# HDMI.net
KiCad netlist of a schematic drawn in Altium Designer
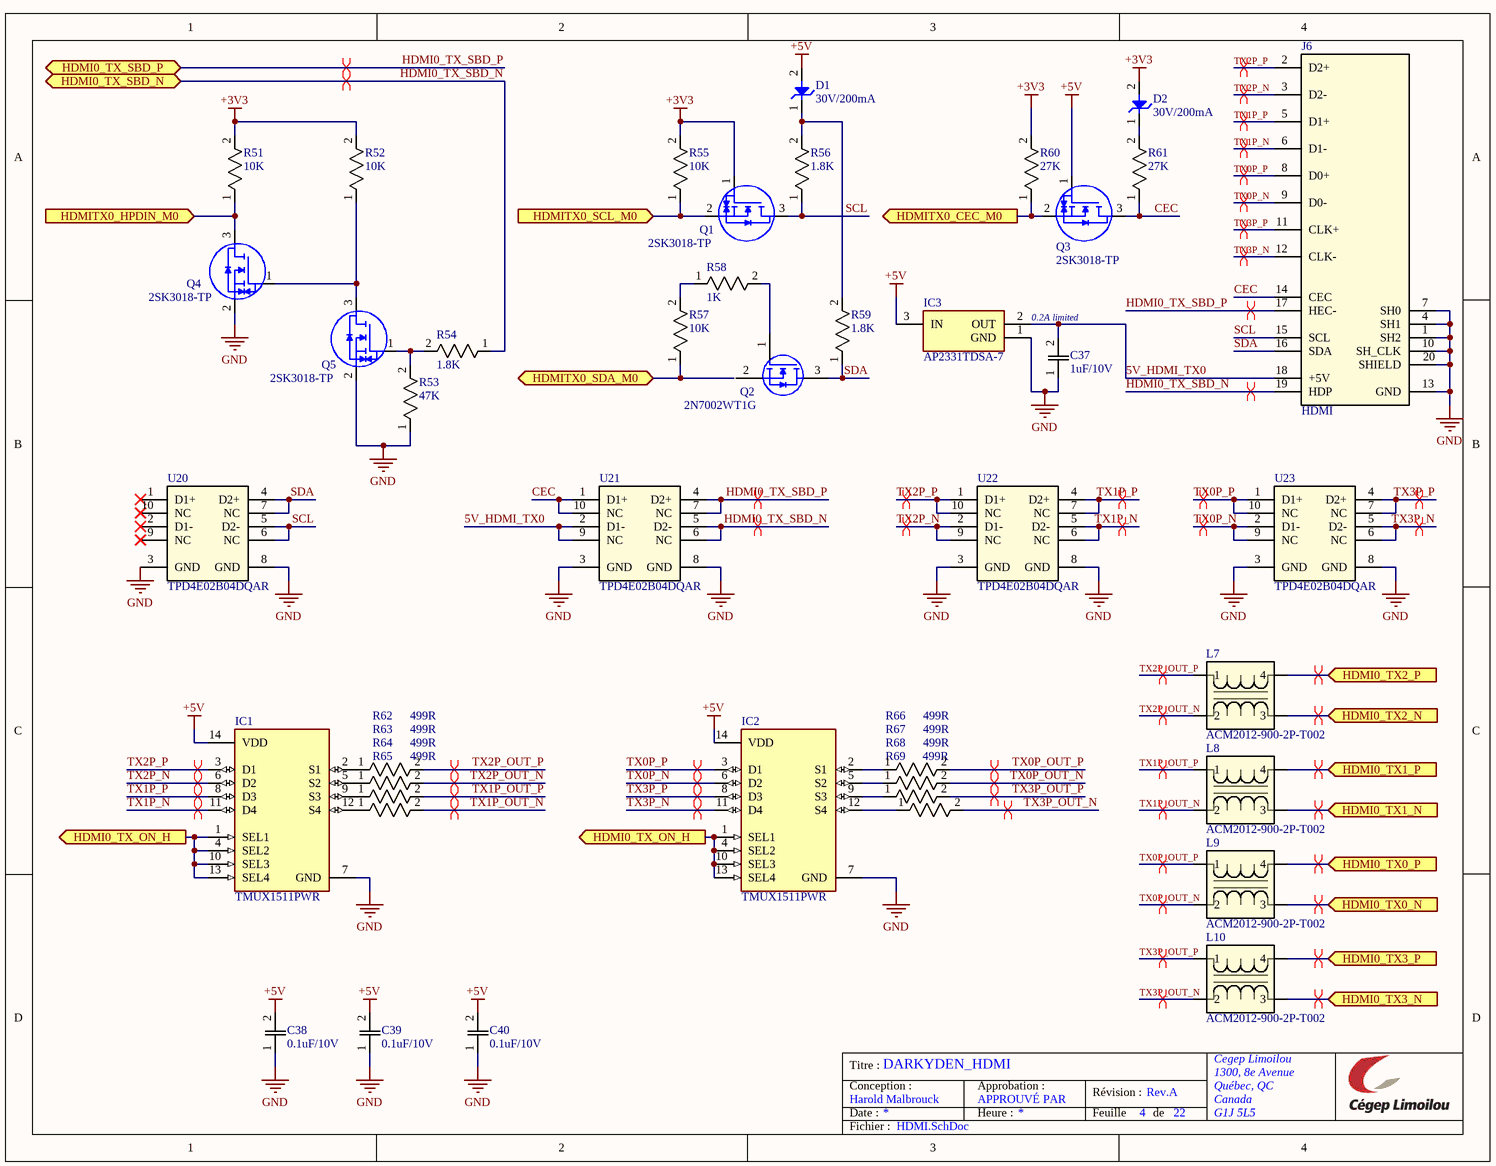
[diagram p0: HDMI.SchDoc]

(export (version "E")
  (design (tool "Eeschema 10.0.6"))
  (components
    (comp (ref "C37")
      (value "1uF/10V")
      (footprint "C0805")
      (description "Multilayer Ceramic Capacitors MLCC - SMD/SMT 10V 1uF X7R 0805 10%")
      (fields
        (field (name "MANUFACTURER") "KEMET")
        (field (name "MANUFACTURER PART NUMBER") "C0805C105K8RACTU")
      )
      (libsource (lib "DARKYDEN") (part "C0805C105K8RACTU"))
    )
    (comp (ref "C38")
      (value "0.1uF/10V")
      (footprint "c0805")
      (description "Cap Ceramic 0.1uF 10V X7R 5% Pad SMD 0805 125C T/R")
      (fields
        (field (name "MANUFACTURER") "KEMET")
        (field (name "MANUFACTURER PART NUMBER") "C0805C104J8RACTU")
      )
      (libsource (lib "DARKYDEN") (part "C0805C104J8RACTU"))
    )
    (comp (ref "C39")
      (value "0.1uF/10V")
      (footprint "c0805")
      (description "Cap Ceramic 0.1uF 10V X7R 5% Pad SMD 0805 125C T/R")
      (fields
        (field (name "MANUFACTURER") "KEMET")
        (field (name "MANUFACTURER PART NUMBER") "C0805C104J8RACTU")
      )
      (libsource (lib "DARKYDEN") (part "C0805C104J8RACTU"))
    )
    (comp (ref "C40")
      (value "0.1uF/10V")
      (footprint "c0805")
      (description "Cap Ceramic 0.1uF 10V X7R 5% Pad SMD 0805 125C T/R")
      (fields
        (field (name "MANUFACTURER") "KEMET")
        (field (name "MANUFACTURER PART NUMBER") "C0805C104J8RACTU")
      )
      (libsource (lib "DARKYDEN") (part "C0805C104J8RACTU"))
    )
    (comp (ref "D1")
      (value "30V/200mA")
      (footprint "SamacSys:SODFL1608X70N")
      (description "SCHOTTKY BARRIER DIODE Rectifier Diode, Schottky, 1 Phase, 1 Element, 0.2A, 30V V(RRM), Silicon")
      (fields
        (field (name "MANUFACTURER_PART_NUMBER") "RB521S30T1G")
        (field (name "MOUSER PART NUMBER") "863-RB521S30T1G")
      )
      (libsource (lib "SamacSys") (part "RB521S30T1G"))
    )
    (comp (ref "D2")
      (value "30V/200mA")
      (footprint "SamacSys:SODFL1608X70N")
      (description "SCHOTTKY BARRIER DIODE Rectifier Diode, Schottky, 1 Phase, 1 Element, 0.2A, 30V V(RRM), Silicon")
      (fields
        (field (name "MANUFACTURER_PART_NUMBER") "RB521S30T1G")
        (field (name "MOUSER PART NUMBER") "863-RB521S30T1G")
      )
      (libsource (lib "SamacSys") (part "RB521S30T1G"))
    )
    (comp (ref "IC1")
      (value "TMUX1511PWR")
      (footprint "SamacSys:SOP65P640X120-14N")
      (fields
        (field (name "MOUSER PART NUMBER") "595-TMUX1511PWR")
        (field (name "MANUFACTURER") "Texas Instruments")
      )
      (libsource (lib "SamacSys") (part "TMUX1511PWR"))
    )
    (comp (ref "IC2")
      (value "TMUX1511PWR")
      (footprint "SamacSys:SOP65P640X120-14N")
      (fields
        (field (name "MOUSER PART NUMBER") "595-TMUX1511PWR")
        (field (name "MANUFACTURER") "Texas Instruments")
      )
      (libsource (lib "SamacSys") (part "TMUX1511PWR"))
    )
    (comp (ref "IC3")
      (value "AP2331TDSA-7")
      (footprint "SamacSys:SOT96P240X110-3N")
      (description "USB Power Switch Single 5.2V 0.4A 3-Pin SOT-23 T/R")
      (fields (field (name "MOUSER PART NUMBER") "621-AP2331TDSA-7") (field (name "MANUFACTURER") "Diodes"))
      (libsource (lib "SamacSys") (part "AP2331TDSA-7"))
    )
    (comp (ref "J6")
      (value "HDMI")
      (footprint "HDMI_MINI")
      (description "Conn Mini HDMI PL 19 POS 0.4mm Solder RA SMD 19 Terminal 1 Port T/R")
      (fields
        (field (name "MANUFACTURER") "Wurth Electronics")
        (field (name "MANUFACTURER PART NUMBER") "685119136923")
      )
      (libsource (lib "DARKYDEN") (part "HDMI"))
    )
    (comp (ref "L7")
      (value "ACM2012-900-2P-T002")
      (footprint "SamacSys:ACM20129002PT002")
      (description "Ferrite Beads Wirewound Common Mode Filter 90Ohm 100MHz 400mA 0805 T/R")
      (fields (field (name "MOUSER PART NUMBER") "810-ACM20129002PT002") (field (name "MANUFACTURER") "TDK"))
      (libsource (lib "SamacSys") (part "ACM2012-900-2P-T002"))
    )
    (comp (ref "L8")
      (value "ACM2012-900-2P-T002")
      (footprint "SamacSys:ACM20129002PT002")
      (description "Ferrite Beads Wirewound Common Mode Filter 90Ohm 100MHz 400mA 0805 T/R")
      (fields (field (name "MOUSER PART NUMBER") "810-ACM20129002PT002") (field (name "MANUFACTURER") "TDK"))
      (libsource (lib "SamacSys") (part "ACM2012-900-2P-T002"))
    )
    (comp (ref "L9")
      (value "ACM2012-900-2P-T002")
      (footprint "SamacSys:ACM20129002PT002")
      (description "Ferrite Beads Wirewound Common Mode Filter 90Ohm 100MHz 400mA 0805 T/R")
      (fields (field (name "MOUSER PART NUMBER") "810-ACM20129002PT002") (field (name "MANUFACTURER") "TDK"))
      (libsource (lib "SamacSys") (part "ACM2012-900-2P-T002"))
    )
    (comp (ref "L10")
      (value "ACM2012-900-2P-T002")
      (footprint "SamacSys:ACM20129002PT002")
      (description "Ferrite Beads Wirewound Common Mode Filter 90Ohm 100MHz 400mA 0805 T/R")
      (fields (field (name "MOUSER PART NUMBER") "810-ACM20129002PT002") (field (name "MANUFACTURER") "TDK"))
      (libsource (lib "SamacSys") (part "ACM2012-900-2P-T002"))
    )
    (comp (ref "Q1")
      (value "2SK3018-TP")
      (footprint "SamacSys:SOT65P228X120-3N")
      (description "N-Channel 30 V 100mA (Ta) 200mW (Ta) Surface Mount SOT-323")
      (fields (field (name "MOUSER PART NUMBER") "833-2SK3018-TP"))
      (libsource (lib "SamacSys") (part "2SK3018-TP"))
    )
    (comp (ref "Q2")
      (value "2N7002WT1G")
      (footprint "SOT-323-3_2P2X1P35_ONS")
      (description "No Description Available")
      (libsource (lib "2N7002WT1G") (part "2N7002WT1G"))
    )
    (comp (ref "Q3")
      (value "2SK3018-TP")
      (footprint "SamacSys:SOT65P228X120-3N")
      (description "N-Channel 30 V 100mA (Ta) 200mW (Ta) Surface Mount SOT-323")
      (fields (field (name "MOUSER PART NUMBER") "833-2SK3018-TP"))
      (libsource (lib "SamacSys") (part "2SK3018-TP"))
    )
    (comp (ref "Q4")
      (value "2SK3018-TP")
      (footprint "SamacSys:SOT65P228X120-3N")
      (description "N-Channel 30 V 100mA (Ta) 200mW (Ta) Surface Mount SOT-323")
      (fields (field (name "MOUSER PART NUMBER") "833-2SK3018-TP"))
      (libsource (lib "SamacSys") (part "2SK3018-TP"))
    )
    (comp (ref "Q5")
      (value "2SK3018-TP")
      (footprint "SamacSys:SOT65P228X120-3N")
      (description "N-Channel 30 V 100mA (Ta) 200mW (Ta) Surface Mount SOT-323")
      (fields (field (name "MOUSER PART NUMBER") "833-2SK3018-TP"))
      (libsource (lib "SamacSys") (part "2SK3018-TP"))
    )
    (comp (ref "R51")
      (value "10K")
      (footprint "SamacSys:RESC1608X55N")
      (description "10K Ohm 5% Res Thick Film 0603  0.1W(1/10W) ±200ppm/C Pad SMD Automotive T/R")
      (fields
        (field (name "MANUFACTURER_PART_NUMBER") "ERJ-3GEYJ103V")
        (field (name "MOUSER PART NUMBER") "667-ERJ-3GEYJ103V")
      )
      (libsource (lib "DARKYDEN") (part "ERJ-3GEYJ103V"))
    )
    (comp (ref "R52")
      (value "10K")
      (footprint "SamacSys:RESC1608X55N")
      (description "10K Ohm 5% Res Thick Film 0603  0.1W(1/10W) ±200ppm/C Pad SMD Automotive T/R")
      (fields
        (field (name "MANUFACTURER_PART_NUMBER") "ERJ-3GEYJ103V")
        (field (name "MOUSER PART NUMBER") "667-ERJ-3GEYJ103V")
      )
      (libsource (lib "DARKYDEN") (part "ERJ-3GEYJ103V"))
    )
    (comp (ref "R53")
      (value "47K")
      (footprint "RESC1608X55N")
      (description "47K Ohm 5% 1/10W 0603 200ppm/C Molded SMD Punched Carrier T/R")
      (fields
        (field (name "MANUFACTURER") "Panasonic")
        (field (name "MANUFACTURER PART NUMBER") "ERJ-3GEYJ473V")
      )
      (libsource (lib "DARKYDEN") (part "ERJ-3GEYJ473V"))
    )
    (comp (ref "R54")
      (value "1.8K")
      (footprint "RESC1608X55N")
      (description "1.8 kOhm, ± 5%, 100 mW, 0603 [1608 Metric], Thick Film, General Purpose")
      (fields
        (field (name "MANUFACTURER") "Panasonic")
        (field (name "MANUFACTURER PART NUMBER") "ERJ-3GEYJ182V")
      )
      (libsource (lib "DARKYDEN") (part "ERJ-3GEYJ182V"))
    )
    (comp (ref "R55")
      (value "10K")
      (footprint "SamacSys:RESC1608X55N")
      (description "10K Ohm 5% Res Thick Film 0603  0.1W(1/10W) ±200ppm/C Pad SMD Automotive T/R")
      (fields
        (field (name "MANUFACTURER_PART_NUMBER") "ERJ-3GEYJ103V")
        (field (name "MOUSER PART NUMBER") "667-ERJ-3GEYJ103V")
      )
      (libsource (lib "DARKYDEN") (part "ERJ-3GEYJ103V"))
    )
    (comp (ref "R56")
      (value "1.8K")
      (footprint "RESC1608X55N")
      (description "1.8 kOhm, ± 5%, 100 mW, 0603 [1608 Metric], Thick Film, General Purpose")
      (fields
        (field (name "MANUFACTURER") "Panasonic")
        (field (name "MANUFACTURER PART NUMBER") "ERJ-3GEYJ182V")
      )
      (libsource (lib "DARKYDEN") (part "ERJ-3GEYJ182V"))
    )
    (comp (ref "R57")
      (value "10K")
      (footprint "SamacSys:RESC1608X55N")
      (description "10K Ohm 5% Res Thick Film 0603  0.1W(1/10W) ±200ppm/C Pad SMD Automotive T/R")
      (fields
        (field (name "MANUFACTURER_PART_NUMBER") "ERJ-3GEYJ103V")
        (field (name "MOUSER PART NUMBER") "667-ERJ-3GEYJ103V")
      )
      (libsource (lib "DARKYDEN") (part "ERJ-3GEYJ103V"))
    )
    (comp (ref "R58")
      (value "1K")
      (footprint "SamacSys:RESC1608X55N")
      (description "1K Ohm 1% 1/10W Res Thick Film 0603 ±100ppm/°C Molded SMD Punched Carrier T/R")
      (fields
        (field (name "MANUFACTURER_PART_NUMBER") "ERJ-3EKF1001V")
        (field (name "MOUSER PART NUMBER") "667-ERJ-3EKF1001V")
      )
      (libsource (lib "DARKYDEN") (part "ERJ-3EKF1001V"))
    )
    (comp (ref "R59")
      (value "1.8K")
      (footprint "RESC1608X55N")
      (description "1.8 kOhm, ± 5%, 100 mW, 0603 [1608 Metric], Thick Film, General Purpose")
      (fields
        (field (name "MANUFACTURER") "Panasonic")
        (field (name "MANUFACTURER PART NUMBER") "ERJ-3GEYJ182V")
      )
      (libsource (lib "DARKYDEN") (part "ERJ-3GEYJ182V"))
    )
    (comp (ref "R60")
      (value "27K")
      (footprint "RESC1608X55N")
      (description "27K Ohm 1% 1/10W 0603 ±100ppm/°C Molded SMD Punched Carrier T/R")
      (fields
        (field (name "MANUFACTURER") "Panasonic")
        (field (name "MANUFACTURER PART NUMBER") "ERJ-3EKF2702V")
      )
      (libsource (lib "DARKYDEN") (part "ERJ-3EKF2702V"))
    )
    (comp (ref "R61")
      (value "27K")
      (footprint "RESC1608X55N")
      (description "27K Ohm 1% 1/10W 0603 ±100ppm/°C Molded SMD Punched Carrier T/R")
      (fields
        (field (name "MANUFACTURER") "Panasonic")
        (field (name "MANUFACTURER PART NUMBER") "ERJ-3EKF2702V")
      )
      (libsource (lib "DARKYDEN") (part "ERJ-3EKF2702V"))
    )
    (comp (ref "R62")
      (value "499R")
      (footprint "RESC1608X55N")
      (description "499 Ohm, ï¿½ 1%, 100 mW, 0603 [1608 Metric], Thick Film, Precision")
      (fields
        (field (name "MANUFACTURER") "Panasonic")
        (field (name "MANUFACTURER PART NUMBER") "ERJ-3EKF4990V")
      )
      (libsource (lib "DARKYDEN") (part "ERJ-3EKF4990V"))
    )
    (comp (ref "R63")
      (value "499R")
      (footprint "RESC1608X55N")
      (description "499 Ohm, ï¿½ 1%, 100 mW, 0603 [1608 Metric], Thick Film, Precision")
      (fields
        (field (name "MANUFACTURER") "Panasonic")
        (field (name "MANUFACTURER PART NUMBER") "ERJ-3EKF4990V")
      )
      (libsource (lib "DARKYDEN") (part "ERJ-3EKF4990V"))
    )
    (comp (ref "R64")
      (value "499R")
      (footprint "RESC1608X55N")
      (description "499 Ohm, ï¿½ 1%, 100 mW, 0603 [1608 Metric], Thick Film, Precision")
      (fields
        (field (name "MANUFACTURER") "Panasonic")
        (field (name "MANUFACTURER PART NUMBER") "ERJ-3EKF4990V")
      )
      (libsource (lib "DARKYDEN") (part "ERJ-3EKF4990V"))
    )
    (comp (ref "R65")
      (value "499R")
      (footprint "RESC1608X55N")
      (description "499 Ohm, ï¿½ 1%, 100 mW, 0603 [1608 Metric], Thick Film, Precision")
      (fields
        (field (name "MANUFACTURER") "Panasonic")
        (field (name "MANUFACTURER PART NUMBER") "ERJ-3EKF4990V")
      )
      (libsource (lib "DARKYDEN") (part "ERJ-3EKF4990V"))
    )
    (comp (ref "R66")
      (value "499R")
      (footprint "RESC1608X55N")
      (description "499 Ohm, ï¿½ 1%, 100 mW, 0603 [1608 Metric], Thick Film, Precision")
      (fields
        (field (name "MANUFACTURER") "Panasonic")
        (field (name "MANUFACTURER PART NUMBER") "ERJ-3EKF4990V")
      )
      (libsource (lib "DARKYDEN") (part "ERJ-3EKF4990V"))
    )
    (comp (ref "R67")
      (value "499R")
      (footprint "RESC1608X55N")
      (description "499 Ohm, ï¿½ 1%, 100 mW, 0603 [1608 Metric], Thick Film, Precision")
      (fields
        (field (name "MANUFACTURER") "Panasonic")
        (field (name "MANUFACTURER PART NUMBER") "ERJ-3EKF4990V")
      )
      (libsource (lib "DARKYDEN") (part "ERJ-3EKF4990V"))
    )
    (comp (ref "R68")
      (value "499R")
      (footprint "RESC1608X55N")
      (description "499 Ohm, ï¿½ 1%, 100 mW, 0603 [1608 Metric], Thick Film, Precision")
      (fields
        (field (name "MANUFACTURER") "Panasonic")
        (field (name "MANUFACTURER PART NUMBER") "ERJ-3EKF4990V")
      )
      (libsource (lib "DARKYDEN") (part "ERJ-3EKF4990V"))
    )
    (comp (ref "R69")
      (value "499R")
      (footprint "RESC1608X55N")
      (description "499 Ohm, ï¿½ 1%, 100 mW, 0603 [1608 Metric], Thick Film, Precision")
      (fields
        (field (name "MANUFACTURER") "Panasonic")
        (field (name "MANUFACTURER PART NUMBER") "ERJ-3EKF4990V")
      )
      (libsource (lib "DARKYDEN") (part "ERJ-3EKF4990V"))
    )
    (comp (ref "U20")
      (value "TPD4E02B04DQAR")
      (footprint "DQA0010A")
      (description "TVS DIODE 3.6V 8.8V 10USON / 4-Channel ESD Protection Diode for USB Type-C and HDMI 2.0")
      (fields (field (name "MANUFACTURER") "Texas Instruments"))
      (libsource (lib "TPD4E02B04DQAR") (part "TPD4E02B04DQAR"))
    )
    (comp (ref "U21")
      (value "TPD4E02B04DQAR")
      (footprint "DQA0010A")
      (description "TVS DIODE 3.6V 8.8V 10USON / 4-Channel ESD Protection Diode for USB Type-C and HDMI 2.0")
      (fields (field (name "MANUFACTURER") "Texas Instruments"))
      (libsource (lib "TPD4E02B04DQAR") (part "TPD4E02B04DQAR"))
    )
    (comp (ref "U22")
      (value "TPD4E02B04DQAR")
      (footprint "DQA0010A")
      (description "TVS DIODE 3.6V 8.8V 10USON / 4-Channel ESD Protection Diode for USB Type-C and HDMI 2.0")
      (fields (field (name "MANUFACTURER") "Texas Instruments"))
      (libsource (lib "TPD4E02B04DQAR") (part "TPD4E02B04DQAR"))
    )
    (comp (ref "U23")
      (value "TPD4E02B04DQAR")
      (footprint "DQA0010A")
      (description "TVS DIODE 3.6V 8.8V 10USON / 4-Channel ESD Protection Diode for USB Type-C and HDMI 2.0")
      (fields (field (name "MANUFACTURER") "Texas Instruments"))
      (libsource (lib "TPD4E02B04DQAR") (part "TPD4E02B04DQAR"))
    )
  )
  (nets
    (net (code "1") (name "+3V3") (class "Default")
      (node (ref "D2") (pin "2") (pinfunction "A_2") (pintype "passive"))
      (node (ref "Q1") (pin "1") (pinfunction "G_1") (pintype "passive"))
      (node (ref "R51") (pin "2") (pinfunction "2_2") (pintype "passive"))
      (node (ref "R52") (pin "2") (pinfunction "2_2") (pintype "passive"))
      (node (ref "R55") (pin "2") (pinfunction "2_2") (pintype "passive"))
      (node (ref "R60") (pin "2") (pinfunction "2_2") (pintype "passive"))
    )
    (net (code "2") (name "+5V") (class "Default")
      (node (ref "C38") (pin "2") (pinfunction "2_2") (pintype "passive"))
      (node (ref "C39") (pin "2") (pinfunction "2_2") (pintype "passive"))
      (node (ref "C40") (pin "2") (pinfunction "2_2") (pintype "passive"))
      (node (ref "D1") (pin "2") (pinfunction "A_2") (pintype "passive"))
      (node (ref "IC1") (pin "14") (pinfunction "VDD_14") (pintype "power_in"))
      (node (ref "IC2") (pin "14") (pinfunction "VDD_14") (pintype "power_in"))
      (node (ref "IC3") (pin "3") (pinfunction "IN_3") (pintype "passive"))
      (node (ref "Q3") (pin "1") (pinfunction "G_1") (pintype "passive"))
    )
    (net (code "3") (name "/5V_HDMI_TX0") (class "Default")
      (node (ref "C37") (pin "2") (pinfunction "2_2") (pintype "passive"))
      (node (ref "IC3") (pin "2") (pinfunction "OUT_2") (pintype "passive"))
      (node (ref "J6") (pin "18") (pinfunction "+5V_18") (pintype "passive"))
      (node (ref "U21") (pin "2") (pinfunction "D1-_2") (pintype "passive"))
      (node (ref "U21") (pin "9") (pinfunction "NC_9") (pintype "passive"))
    )
    (net (code "4") (name "/CEC") (class "Default")
      (node (ref "J6") (pin "14") (pinfunction "CEC_14") (pintype "passive"))
      (node (ref "Q3") (pin "3") (pinfunction "D_3") (pintype "passive"))
      (node (ref "R61") (pin "1") (pinfunction "1_1") (pintype "passive"))
      (node (ref "U21") (pin "1") (pinfunction "D1+_1") (pintype "passive"))
      (node (ref "U21") (pin "10") (pinfunction "NC_10") (pintype "passive"))
    )
    (net (code "5") (name "/HDMI0_TX0_N") (class "Default")
      (node (ref "L9") (pin "3") (pinfunction "3_3") (pintype "passive"))
    )
    (net (code "6") (name "/HDMI0_TX0_P") (class "Default")
      (node (ref "L9") (pin "4") (pinfunction "4_4") (pintype "passive"))
    )
    (net (code "7") (name "/HDMI0_TX1_N") (class "Default")
      (node (ref "L8") (pin "3") (pinfunction "3_3") (pintype "passive"))
    )
    (net (code "8") (name "/HDMI0_TX1_P") (class "Default")
      (node (ref "L8") (pin "4") (pinfunction "4_4") (pintype "passive"))
    )
    (net (code "9") (name "/HDMI0_TX2_N") (class "Default")
      (node (ref "L7") (pin "3") (pinfunction "3_3") (pintype "passive"))
    )
    (net (code "10") (name "/HDMI0_TX2_P") (class "Default")
      (node (ref "L7") (pin "4") (pinfunction "4_4") (pintype "passive"))
    )
    (net (code "11") (name "/HDMI0_TX3_N") (class "Default")
      (node (ref "L10") (pin "3") (pinfunction "3_3") (pintype "passive"))
    )
    (net (code "12") (name "/HDMI0_TX3_P") (class "Default")
      (node (ref "L10") (pin "4") (pinfunction "4_4") (pintype "passive"))
    )
    (net (code "13") (name "/HDMI0_TX_ON_H") (class "Default")
      (node (ref "IC1") (pin "1") (pinfunction "SEL1_1") (pintype "input"))
      (node (ref "IC1") (pin "10") (pinfunction "SEL3_10") (pintype "input"))
      (node (ref "IC1") (pin "13") (pinfunction "SEL4_13") (pintype "input"))
      (node (ref "IC1") (pin "4") (pinfunction "SEL2_4") (pintype "input"))
      (node (ref "IC2") (pin "1") (pinfunction "SEL1_1") (pintype "input"))
      (node (ref "IC2") (pin "10") (pinfunction "SEL3_10") (pintype "input"))
      (node (ref "IC2") (pin "13") (pinfunction "SEL4_13") (pintype "input"))
      (node (ref "IC2") (pin "4") (pinfunction "SEL2_4") (pintype "input"))
    )
    (net (code "14") (name "/HDMI0_TX_SBD_N") (class "Default")
      (node (ref "J6") (pin "19") (pinfunction "HDP_19") (pintype "passive"))
      (node (ref "R54") (pin "1") (pinfunction "1_1") (pintype "passive"))
      (node (ref "U21") (pin "5") (pinfunction "D2-_5") (pintype "passive"))
      (node (ref "U21") (pin "6") (pinfunction "NC_6") (pintype "passive"))
    )
    (net (code "15") (name "/HDMI0_TX_SBD_P") (class "Default")
      (node (ref "J6") (pin "17") (pinfunction "HEC-_17") (pintype "passive"))
      (node (ref "U21") (pin "4") (pinfunction "D2+_4") (pintype "passive"))
      (node (ref "U21") (pin "7") (pinfunction "NC_7") (pintype "passive"))
    )
    (net (code "16") (name "/HDMITX0_CEC_M0") (class "Default")
      (node (ref "Q3") (pin "2") (pinfunction "S_2") (pintype "passive"))
      (node (ref "R60") (pin "1") (pinfunction "1_1") (pintype "passive"))
    )
    (net (code "17") (name "/HDMITX0_HPDIN_M0") (class "Default")
      (node (ref "Q4") (pin "3") (pinfunction "D_3") (pintype "passive"))
      (node (ref "R51") (pin "1") (pinfunction "1_1") (pintype "passive"))
    )
    (net (code "18") (name "/HDMITX0_SCL_M0") (class "Default")
      (node (ref "Q1") (pin "2") (pinfunction "S_2") (pintype "passive"))
      (node (ref "R55") (pin "1") (pinfunction "1_1") (pintype "passive"))
    )
    (net (code "19") (name "/HDMITX0_SDA_M0") (class "Default")
      (node (ref "R57") (pin "1") (pinfunction "1_1") (pintype "passive"))
    )
    (net (code "20") (name "/SCL") (class "Default")
      (node (ref "J6") (pin "15") (pinfunction "SCL_15") (pintype "passive"))
      (node (ref "Q1") (pin "3") (pinfunction "D_3") (pintype "passive"))
      (node (ref "R56") (pin "1") (pinfunction "1_1") (pintype "passive"))
      (node (ref "U20") (pin "5") (pinfunction "D2-_5") (pintype "passive"))
      (node (ref "U20") (pin "6") (pinfunction "NC_6") (pintype "passive"))
    )
    (net (code "21") (name "/SDA") (class "Default")
      (node (ref "J6") (pin "16") (pinfunction "SDA_16") (pintype "passive"))
      (node (ref "Q2") (pin "3") (pinfunction "DRAIN_3") (pintype "passive"))
      (node (ref "R59") (pin "1") (pinfunction "1_1") (pintype "passive"))
      (node (ref "U20") (pin "4") (pinfunction "D2+_4") (pintype "passive"))
      (node (ref "U20") (pin "7") (pinfunction "NC_7") (pintype "passive"))
    )
    (net (code "22") (name "/TX0P_N") (class "Default")
      (node (ref "IC2") (pin "6") (pinfunction "D2_6") (pintype "bidirectional"))
      (node (ref "J6") (pin "9") (pinfunction "D0-_9") (pintype "passive"))
      (node (ref "U23") (pin "2") (pinfunction "D1-_2") (pintype "passive"))
      (node (ref "U23") (pin "9") (pinfunction "NC_9") (pintype "passive"))
    )
    (net (code "23") (name "/TX0P_OUT_N") (class "Default")
      (node (ref "L9") (pin "2") (pinfunction "2_2") (pintype "passive"))
      (node (ref "R67") (pin "2") (pinfunction "2_2") (pintype "passive"))
    )
    (net (code "24") (name "/TX0P_OUT_P") (class "Default")
      (node (ref "L9") (pin "1") (pinfunction "1_1") (pintype "passive"))
      (node (ref "R66") (pin "2") (pinfunction "2_2") (pintype "passive"))
    )
    (net (code "25") (name "/TX0P_P") (class "Default")
      (node (ref "IC2") (pin "3") (pinfunction "D1_3") (pintype "bidirectional"))
      (node (ref "J6") (pin "8") (pinfunction "D0+_8") (pintype "passive"))
      (node (ref "U23") (pin "1") (pinfunction "D1+_1") (pintype "passive"))
      (node (ref "U23") (pin "10") (pinfunction "NC_10") (pintype "passive"))
    )
    (net (code "26") (name "/TX1P_N") (class "Default")
      (node (ref "IC1") (pin "11") (pinfunction "D4_11") (pintype "bidirectional"))
      (node (ref "J6") (pin "6") (pinfunction "D1-_6") (pintype "passive"))
      (node (ref "U22") (pin "5") (pinfunction "D2-_5") (pintype "passive"))
      (node (ref "U22") (pin "6") (pinfunction "NC_6") (pintype "passive"))
    )
    (net (code "27") (name "/TX1P_OUT_N") (class "Default")
      (node (ref "L8") (pin "2") (pinfunction "2_2") (pintype "passive"))
      (node (ref "R65") (pin "2") (pinfunction "2_2") (pintype "passive"))
    )
    (net (code "28") (name "/TX1P_OUT_P") (class "Default")
      (node (ref "L8") (pin "1") (pinfunction "1_1") (pintype "passive"))
      (node (ref "R64") (pin "2") (pinfunction "2_2") (pintype "passive"))
    )
    (net (code "29") (name "/TX1P_P") (class "Default")
      (node (ref "IC1") (pin "8") (pinfunction "D3_8") (pintype "bidirectional"))
      (node (ref "J6") (pin "5") (pinfunction "D1+_5") (pintype "passive"))
      (node (ref "U22") (pin "4") (pinfunction "D2+_4") (pintype "passive"))
      (node (ref "U22") (pin "7") (pinfunction "NC_7") (pintype "passive"))
    )
    (net (code "30") (name "/TX2P_N") (class "Default")
      (node (ref "IC1") (pin "6") (pinfunction "D2_6") (pintype "bidirectional"))
      (node (ref "J6") (pin "3") (pinfunction "D2-_3") (pintype "passive"))
      (node (ref "U22") (pin "2") (pinfunction "D1-_2") (pintype "passive"))
      (node (ref "U22") (pin "9") (pinfunction "NC_9") (pintype "passive"))
    )
    (net (code "31") (name "/TX2P_OUT_N") (class "Default")
      (node (ref "L7") (pin "2") (pinfunction "2_2") (pintype "passive"))
      (node (ref "R63") (pin "2") (pinfunction "2_2") (pintype "passive"))
    )
    (net (code "32") (name "/TX2P_OUT_P") (class "Default")
      (node (ref "L7") (pin "1") (pinfunction "1_1") (pintype "passive"))
      (node (ref "R62") (pin "2") (pinfunction "2_2") (pintype "passive"))
    )
    (net (code "33") (name "/TX2P_P") (class "Default")
      (node (ref "IC1") (pin "3") (pinfunction "D1_3") (pintype "bidirectional"))
      (node (ref "J6") (pin "2") (pinfunction "D2+_2") (pintype "passive"))
      (node (ref "U22") (pin "1") (pinfunction "D1+_1") (pintype "passive"))
      (node (ref "U22") (pin "10") (pinfunction "NC_10") (pintype "passive"))
    )
    (net (code "34") (name "/TX3P_N") (class "Default")
      (node (ref "IC2") (pin "11") (pinfunction "D4_11") (pintype "bidirectional"))
      (node (ref "J6") (pin "12") (pinfunction "CLK-_12") (pintype "passive"))
      (node (ref "U23") (pin "5") (pinfunction "D2-_5") (pintype "passive"))
      (node (ref "U23") (pin "6") (pinfunction "NC_6") (pintype "passive"))
    )
    (net (code "35") (name "/TX3P_OUT_N") (class "Default")
      (node (ref "L10") (pin "2") (pinfunction "2_2") (pintype "passive"))
      (node (ref "R69") (pin "2") (pinfunction "2_2") (pintype "passive"))
    )
    (net (code "36") (name "/TX3P_OUT_P") (class "Default")
      (node (ref "L10") (pin "1") (pinfunction "1_1") (pintype "passive"))
      (node (ref "R68") (pin "2") (pinfunction "2_2") (pintype "passive"))
    )
    (net (code "37") (name "/TX3P_P") (class "Default")
      (node (ref "IC2") (pin "8") (pinfunction "D3_8") (pintype "bidirectional"))
      (node (ref "J6") (pin "11") (pinfunction "CLK+_11") (pintype "passive"))
      (node (ref "U23") (pin "4") (pinfunction "D2+_4") (pintype "passive"))
      (node (ref "U23") (pin "7") (pinfunction "NC_7") (pintype "passive"))
    )
    (net (code "38") (name "GND") (class "Default")
      (node (ref "C37") (pin "1") (pinfunction "1_1") (pintype "passive"))
      (node (ref "C38") (pin "1") (pinfunction "1_1") (pintype "passive"))
      (node (ref "C39") (pin "1") (pinfunction "1_1") (pintype "passive"))
      (node (ref "C40") (pin "1") (pinfunction "1_1") (pintype "passive"))
      (node (ref "IC1") (pin "7") (pinfunction "GND_7") (pintype "power_in"))
      (node (ref "IC2") (pin "7") (pinfunction "GND_7") (pintype "power_in"))
      (node (ref "IC3") (pin "1") (pinfunction "GND_1") (pintype "passive"))
      (node (ref "J6") (pin "1") (pinfunction "SH2_1") (pintype "passive"))
      (node (ref "J6") (pin "10") (pinfunction "SH_CLK_10") (pintype "passive"))
      (node (ref "J6") (pin "13") (pinfunction "GND_13") (pintype "passive"))
      (node (ref "J6") (pin "20") (pinfunction "SHIELD_20") (pintype "passive"))
      (node (ref "J6") (pin "4") (pinfunction "SH1_4") (pintype "passive"))
      (node (ref "J6") (pin "7") (pinfunction "SH0_7") (pintype "passive"))
      (node (ref "Q4") (pin "2") (pinfunction "S_2") (pintype "passive"))
      (node (ref "Q5") (pin "2") (pinfunction "S_2") (pintype "passive"))
      (node (ref "R53") (pin "1") (pinfunction "1_1") (pintype "passive"))
      (node (ref "U20") (pin "3") (pinfunction "GND_3") (pintype "passive"))
      (node (ref "U20") (pin "8") (pinfunction "GND_8") (pintype "passive"))
      (node (ref "U21") (pin "3") (pinfunction "GND_3") (pintype "passive"))
      (node (ref "U21") (pin "8") (pinfunction "GND_8") (pintype "passive"))
      (node (ref "U22") (pin "3") (pinfunction "GND_3") (pintype "passive"))
      (node (ref "U22") (pin "8") (pinfunction "GND_8") (pintype "passive"))
      (node (ref "U23") (pin "3") (pinfunction "GND_3") (pintype "passive"))
      (node (ref "U23") (pin "8") (pinfunction "GND_8") (pintype "passive"))
    )
    (net (code "39") (name "Net-(D1-K)") (class "Default")
      (node (ref "D1") (pin "1") (pinfunction "K_1") (pintype "passive"))
      (node (ref "R56") (pin "2") (pinfunction "2_2") (pintype "passive"))
      (node (ref "R59") (pin "2") (pinfunction "2_2") (pintype "passive"))
    )
    (net (code "40") (name "Net-(D2-K)") (class "Default")
      (node (ref "D2") (pin "1") (pinfunction "K_1") (pintype "passive"))
      (node (ref "R61") (pin "2") (pinfunction "2_2") (pintype "passive"))
    )
    (net (code "41") (name "Net-(IC1-S1)") (class "Default")
      (node (ref "IC1") (pin "2") (pinfunction "S1_2") (pintype "bidirectional"))
      (node (ref "R62") (pin "1") (pinfunction "1_1") (pintype "passive"))
    )
    (net (code "42") (name "Net-(IC1-S2)") (class "Default")
      (node (ref "IC1") (pin "5") (pinfunction "S2_5") (pintype "bidirectional"))
      (node (ref "R63") (pin "1") (pinfunction "1_1") (pintype "passive"))
    )
    (net (code "43") (name "Net-(IC1-S3)") (class "Default")
      (node (ref "IC1") (pin "9") (pinfunction "S3_9") (pintype "bidirectional"))
      (node (ref "R64") (pin "1") (pinfunction "1_1") (pintype "passive"))
    )
    (net (code "44") (name "Net-(IC1-S4)") (class "Default")
      (node (ref "IC1") (pin "12") (pinfunction "S4_12") (pintype "bidirectional"))
      (node (ref "R65") (pin "1") (pinfunction "1_1") (pintype "passive"))
    )
    (net (code "45") (name "Net-(IC2-S1)") (class "Default")
      (node (ref "IC2") (pin "2") (pinfunction "S1_2") (pintype "bidirectional"))
      (node (ref "R66") (pin "1") (pinfunction "1_1") (pintype "passive"))
    )
    (net (code "46") (name "Net-(IC2-S2)") (class "Default")
      (node (ref "IC2") (pin "5") (pinfunction "S2_5") (pintype "bidirectional"))
      (node (ref "R67") (pin "1") (pinfunction "1_1") (pintype "passive"))
    )
    (net (code "47") (name "Net-(IC2-S3)") (class "Default")
      (node (ref "IC2") (pin "9") (pinfunction "S3_9") (pintype "bidirectional"))
      (node (ref "R68") (pin "1") (pinfunction "1_1") (pintype "passive"))
    )
    (net (code "48") (name "Net-(IC2-S4)") (class "Default")
      (node (ref "IC2") (pin "12") (pinfunction "S4_12") (pintype "bidirectional"))
      (node (ref "R69") (pin "1") (pinfunction "1_1") (pintype "passive"))
    )
    (net (code "49") (name "Net-(Q2-GATE)") (class "Default")
      (node (ref "Q2") (pin "1") (pinfunction "GATE_1") (pintype "passive"))
      (node (ref "R58") (pin "2") (pinfunction "2_2") (pintype "passive"))
    )
    (net (code "50") (name "Net-(Q4-G)") (class "Default")
      (node (ref "Q4") (pin "1") (pinfunction "G_1") (pintype "passive"))
      (node (ref "Q5") (pin "3") (pinfunction "D_3") (pintype "passive"))
      (node (ref "R52") (pin "1") (pinfunction "1_1") (pintype "passive"))
    )
    (net (code "51") (name "Net-(Q5-G)") (class "Default")
      (node (ref "Q5") (pin "1") (pinfunction "G_1") (pintype "passive"))
      (node (ref "R53") (pin "2") (pinfunction "2_2") (pintype "passive"))
      (node (ref "R54") (pin "2") (pinfunction "2_2") (pintype "passive"))
    )
    (net (code "52") (name "Net-(R57-Pad2)") (class "Default")
      (node (ref "R57") (pin "2") (pinfunction "2_2") (pintype "passive"))
      (node (ref "R58") (pin "1") (pinfunction "1_1") (pintype "passive"))
    )
    (net (code "53") (name "unconnected-(Q2-SOURCE-Pad2)") (class "Default")
      (node (ref "Q2") (pin "2") (pinfunction "SOURCE_2") (pintype "passive"))
    )
    (net (code "54") (name "unconnected-(U20-D1+-Pad1)") (class "Default")
      (node (ref "U20") (pin "1") (pinfunction "D1+_1") (pintype "passive+no_connect"))
    )
    (net (code "55") (name "unconnected-(U20-D1--Pad2)") (class "Default")
      (node (ref "U20") (pin "2") (pinfunction "D1-_2") (pintype "passive+no_connect"))
    )
    (net (code "56") (name "unconnected-(U20-NC-Pad9)") (class "Default")
      (node (ref "U20") (pin "9") (pinfunction "NC_9") (pintype "passive+no_connect"))
    )
    (net (code "57") (name "unconnected-(U20-NC-Pad10)") (class "Default")
      (node (ref "U20") (pin "10") (pinfunction "NC_10") (pintype "passive+no_connect"))
    )
  )
)
